# PWR_input_connector.net
KiCad netlist of a schematic drawn in Altium Designer
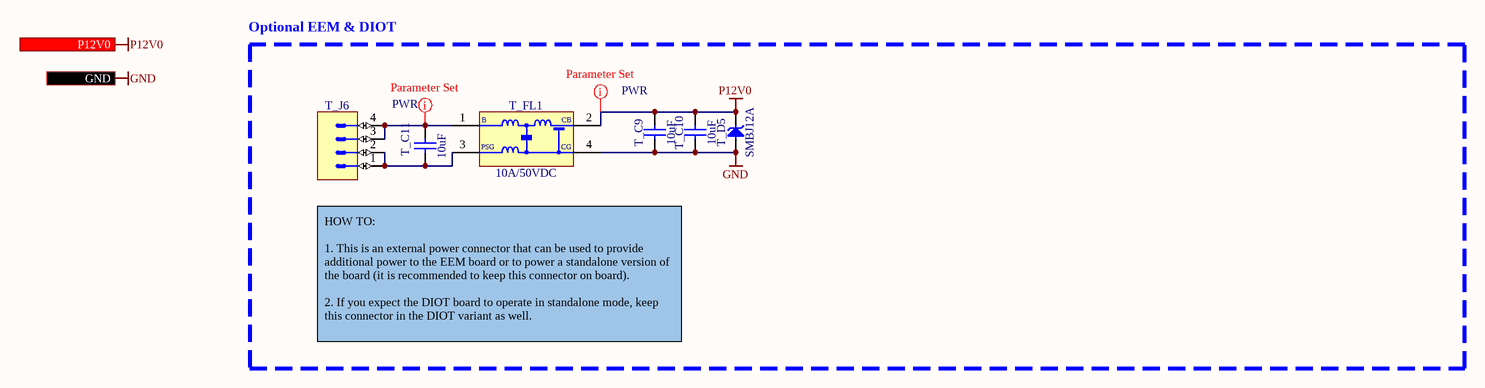
[diagram p0: PWR_input_connector.SchDoc]

(export (version "E")
  (design (tool "Eeschema 10.0.6"))
  (components
    (comp (ref "T_C9")
      (value "10uF")
      (footprint "CAPC2012X95N")
      (description "Non-polarised capacitor")
      (fields
        (field (name "PART NUMBER") "CC0805_10UF_25V_10%_X5R")
        (field (name "VOLTAGE") "25V")
        (field (name "AUTHOR") "CERN DEM JLC")
      )
      (libsource (lib "Capacitors") (part "Capacitor - non polarized"))
    )
    (comp (ref "T_C10")
      (value "10uF")
      (footprint "CAPC2012X95N")
      (description "Non-polarised capacitor")
      (fields
        (field (name "PART NUMBER") "CC0805_10UF_25V_10%_X5R")
        (field (name "VOLTAGE") "25V")
        (field (name "AUTHOR") "CERN DEM JLC")
      )
      (libsource (lib "Capacitors") (part "Capacitor - non polarized"))
    )
    (comp (ref "T_C11")
      (value "10uF")
      (footprint "CAPC2012X95N")
      (description "Non-polarised capacitor")
      (fields
        (field (name "PART NUMBER") "CC0805_10UF_25V_10%_X5R")
        (field (name "VOLTAGE") "25V")
        (field (name "AUTHOR") "CERN DEM JLC")
      )
      (libsource (lib "Capacitors") (part "Capacitor - non polarized"))
    )
    (comp (ref "T_D5")
      (value "SMBJ12A")
      (footprint "DIOM5336X265N")
      (description "Zener Diode")
      (fields
        (field (name "VOLTAGE") "12V")
        (field (name "POWER") "600W")
        (field (name "AUTHOR") "CERN DEM JLC")
      )
      (libsource (lib "ICs And Semiconductors") (part "Diode Zener"))
    )
    (comp (ref "T_FL1")
      (value "10A/50VDC")
      (footprint "FIL_MURATA_BNX02")
      (description "Block Type EMIFIL (LC Combined)")
      (fields
        (field (name "PART NUMBER") "FIL_MURATA_BNX022-01L")
        (field (name "MANUFACTURER") "MURATA")
        (field (name "AUTHOR") "CERN DEM JLC")
      )
      (libsource (lib "Inductors & Transformers") (part "FIL_MURATA_BNX02"))
    )
    (comp (ref "T_J6")
      (value "Mini-Fit Jr.™")
      (footprint "MOLEX_39-30-0040")
      (description "Connector 4 Male")
      (fields
        (field (name "PART NUMBER") "MOLEX_39-30-0040")
        (field (name "MANUFACTURER") "MOLEX")
        (field (name "AUTHOR") "CERN DEM JLC")
      )
      (libsource (lib "Connectors") (part "Connector 4 Male"))
    )
  )
  (nets
    (net (code "1") (name "GND") (class "Default")
      (node (ref "T_C10") (pin "1") (pinfunction "1_1") (pintype "passive"))
      (node (ref "T_C9") (pin "1") (pinfunction "1_1") (pintype "passive"))
      (node (ref "T_D5") (pin "2") (pinfunction "A_2") (pintype "passive"))
      (node (ref "T_FL1") (pin "4") (pinfunction "CG_4") (pintype "passive"))
    )
    (net (code "2") (name "Net-(T_FL1-B)") (class "Default")
      (node (ref "T_C11") (pin "2") (pinfunction "2_2") (pintype "passive"))
      (node (ref "T_FL1") (pin "1") (pinfunction "B_1") (pintype "passive"))
      (node (ref "T_J6") (pin "3") (pinfunction "3_3") (pintype "bidirectional"))
      (node (ref "T_J6") (pin "4") (pinfunction "4_4") (pintype "bidirectional"))
    )
    (net (code "3") (name "Net-(T_FL1-PSG)") (class "Default")
      (node (ref "T_C11") (pin "1") (pinfunction "1_1") (pintype "passive"))
      (node (ref "T_FL1") (pin "3") (pinfunction "PSG_3") (pintype "passive"))
      (node (ref "T_J6") (pin "1") (pinfunction "1_1") (pintype "bidirectional"))
      (node (ref "T_J6") (pin "2") (pinfunction "2_2") (pintype "bidirectional"))
    )
    (net (code "4") (name "P12V0") (class "Default")
      (node (ref "T_C10") (pin "2") (pinfunction "2_2") (pintype "passive"))
      (node (ref "T_C9") (pin "2") (pinfunction "2_2") (pintype "passive"))
      (node (ref "T_D5") (pin "1") (pinfunction "C_1") (pintype "passive"))
      (node (ref "T_FL1") (pin "2") (pinfunction "CB_2") (pintype "passive"))
    )
  )
)
